# Channels_1_2.net
KiCad netlist of a schematic drawn in Altium Designer
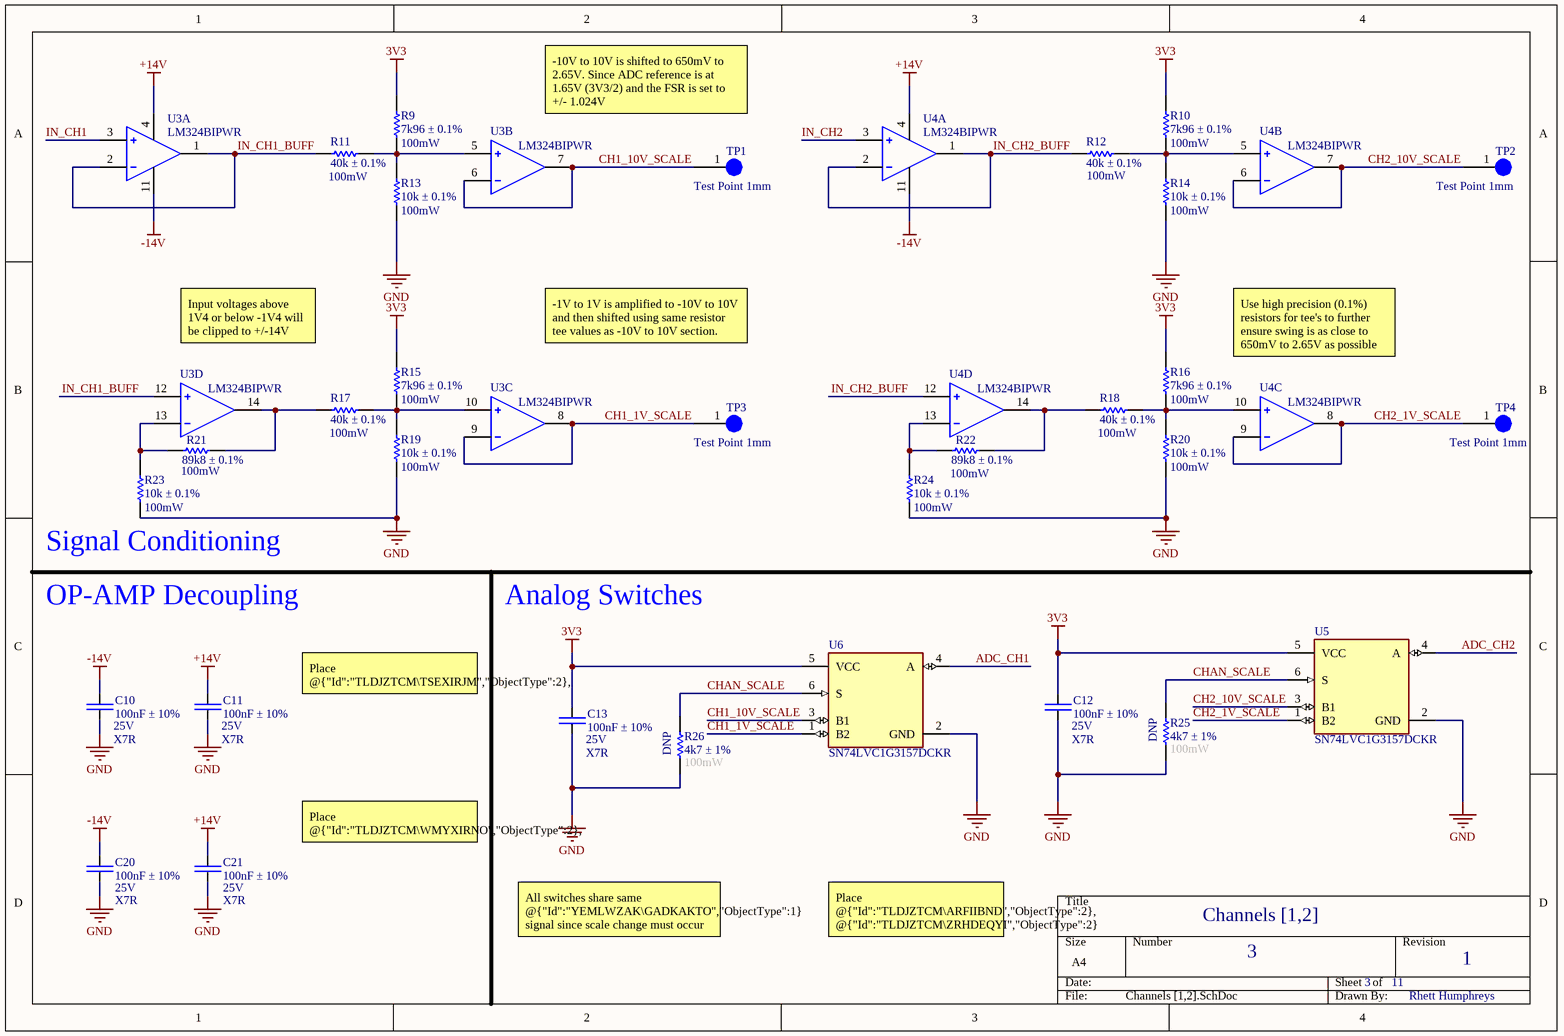
[diagram p0: Channels [1,2].SchDoc]

(export (version "E")
  (design (tool "Eeschema 10.0.6"))
  (components
    (comp (ref "C10")
      (value "100nF ± 10%")
      (footprint "CAP-0603")
      (description "Capacitor chip unpolarized. 0603")
      (libsource (lib "Master") (part "CAP-0603"))
    )
    (comp (ref "C11")
      (value "100nF ± 10%")
      (footprint "CAP-0603")
      (description "Capacitor chip unpolarized. 0603")
      (libsource (lib "Master") (part "CAP-0603"))
    )
    (comp (ref "C12")
      (value "100nF ± 10%")
      (footprint "CAP-0603")
      (description "Capacitor chip unpolarized. 0603")
      (libsource (lib "Master") (part "CAP-0603"))
    )
    (comp (ref "C13")
      (value "100nF ± 10%")
      (footprint "CAP-0603")
      (description "Capacitor chip unpolarized. 0603")
      (libsource (lib "Master") (part "CAP-0603"))
    )
    (comp (ref "C20")
      (value "100nF ± 10%")
      (footprint "CAP-0603")
      (description "Capacitor chip unpolarized. 0603")
      (libsource (lib "Master") (part "CAP-0603"))
    )
    (comp (ref "C21")
      (value "100nF ± 10%")
      (footprint "CAP-0603")
      (description "Capacitor chip unpolarized. 0603")
      (libsource (lib "Master") (part "CAP-0603"))
    )
    (comp (ref "R9")
      (value "7k96 ± 0.1%")
      (footprint "RES-0603")
      (description "Resistor chip. 0603")
      (libsource (lib "Master") (part "RES-0603"))
    )
    (comp (ref "R10")
      (value "7k96 ± 0.1%")
      (footprint "RES-0603")
      (description "Resistor chip. 0603")
      (libsource (lib "Master") (part "RES-0603"))
    )
    (comp (ref "R11")
      (value "40k ± 0.1%")
      (footprint "RES-0603")
      (description "Resistor chip. 0603")
      (libsource (lib "Master") (part "RES-0603"))
    )
    (comp (ref "R12")
      (value "40k ± 0.1%")
      (footprint "RES-0603")
      (description "Resistor chip. 0603")
      (libsource (lib "Master") (part "RES-0603"))
    )
    (comp (ref "R13")
      (value "10k ± 0.1%")
      (footprint "RES-0603")
      (description "Resistor chip. 0603")
      (libsource (lib "Master") (part "RES-0603"))
    )
    (comp (ref "R14")
      (value "10k ± 0.1%")
      (footprint "RES-0603")
      (description "Resistor chip. 0603")
      (libsource (lib "Master") (part "RES-0603"))
    )
    (comp (ref "R15")
      (value "7k96 ± 0.1%")
      (footprint "RES-0603")
      (description "Resistor chip. 0603")
      (libsource (lib "Master") (part "RES-0603"))
    )
    (comp (ref "R16")
      (value "7k96 ± 0.1%")
      (footprint "RES-0603")
      (description "Resistor chip. 0603")
      (libsource (lib "Master") (part "RES-0603"))
    )
    (comp (ref "R17")
      (value "40k ± 0.1%")
      (footprint "RES-0603")
      (description "Resistor chip. 0603")
      (libsource (lib "Master") (part "RES-0603"))
    )
    (comp (ref "R18")
      (value "40k ± 0.1%")
      (footprint "RES-0603")
      (description "Resistor chip. 0603")
      (libsource (lib "Master") (part "RES-0603"))
    )
    (comp (ref "R19")
      (value "10k ± 0.1%")
      (footprint "RES-0603")
      (description "Resistor chip. 0603")
      (libsource (lib "Master") (part "RES-0603"))
    )
    (comp (ref "R20")
      (value "10k ± 0.1%")
      (footprint "RES-0603")
      (description "Resistor chip. 0603")
      (libsource (lib "Master") (part "RES-0603"))
    )
    (comp (ref "R21")
      (value "89k8 ± 0.1%")
      (footprint "RES-0603")
      (description "Resistor chip. 0603")
      (libsource (lib "Master") (part "RES-0603"))
    )
    (comp (ref "R22")
      (value "89k8 ± 0.1%")
      (footprint "RES-0603")
      (description "Resistor chip. 0603")
      (libsource (lib "Master") (part "RES-0603"))
    )
    (comp (ref "R23")
      (value "10k ± 0.1%")
      (footprint "RES-0603")
      (description "Resistor chip. 0603")
      (libsource (lib "Master") (part "RES-0603"))
    )
    (comp (ref "R24")
      (value "10k ± 0.1%")
      (footprint "RES-0603")
      (description "Resistor chip. 0603")
      (libsource (lib "Master") (part "RES-0603"))
    )
    (comp (ref "R25")
      (value "4k7 ± 1%")
      (footprint "RES-0603")
      (description "Resistor chip. 0603")
      (libsource (lib "Master") (part "RES-0603"))
    )
    (comp (ref "R26")
      (value "4k7 ± 1%")
      (footprint "RES-0603")
      (description "Resistor chip. 0603")
      (libsource (lib "Master") (part "RES-0603"))
    )
    (comp (ref "TP1")
      (value "Test Point 1mm")
      (footprint "Test Point 1mm")
      (libsource (lib "Master") (part "Test Point 1mm"))
    )
    (comp (ref "TP2")
      (value "Test Point 1mm")
      (footprint "Test Point 1mm")
      (libsource (lib "Master") (part "Test Point 1mm"))
    )
    (comp (ref "TP3")
      (value "Test Point 1mm")
      (footprint "Test Point 1mm")
      (libsource (lib "Master") (part "Test Point 1mm"))
    )
    (comp (ref "TP4")
      (value "Test Point 1mm")
      (footprint "Test Point 1mm")
      (libsource (lib "Master") (part "Test Point 1mm"))
    )
    (comp (ref "U3")
      (value "LM324BIPWR")
      (footprint "FP-PW0014A-MFG")
      (description "LM324BIPWR Quad, 36-V, 1.2-MHz 3-mV offset voltage operational amplifier 14-TSSOP -40 to 85")
      (libsource (lib "Altium Content Vault") (part "9bf548ecc718f14caecb3de0839edcd"))
    )
    (comp (ref "U4")
      (value "LM324BIPWR")
      (footprint "FP-PW0014A-MFG")
      (description "LM324BIPWR Quad, 36-V, 1.2-MHz 3-mV offset voltage operational amplifier 14-TSSOP -40 to 85")
      (libsource (lib "Altium Content Vault") (part "9bf548ecc718f14caecb3de0839edcd"))
    )
    (comp (ref "U5")
      (value "SN74LVC1G3157DCKR")
      (footprint "FP-DCK0006A-IPC_B")
      (description "IC SWITCH SPDT SC70-6")
      (libsource (lib "Altium Content Vault") (part "0261a57985ab8eeec66806cf7caee19"))
    )
    (comp (ref "U6")
      (value "SN74LVC1G3157DCKR")
      (footprint "FP-DCK0006A-IPC_B")
      (description "IC SWITCH SPDT SC70-6")
      (libsource (lib "Altium Content Vault") (part "0261a57985ab8eeec66806cf7caee19"))
    )
  )
  (nets
    (net (code "1") (name "+14V") (class "Default")
      (node (ref "C11") (pin "2") (pintype "passive"))
      (node (ref "C21") (pin "2") (pintype "passive"))
      (node (ref "U3") (pin "4") (pinfunction "VCC+_4") (pintype "power_in"))
      (node (ref "U4") (pin "4") (pinfunction "VCC+_4") (pintype "power_in"))
    )
    (net (code "2") (name "-14V") (class "Default")
      (node (ref "C10") (pin "2") (pintype "passive"))
      (node (ref "C20") (pin "2") (pintype "passive"))
      (node (ref "U3") (pin "11") (pinfunction "VCC-_11") (pintype "power_in"))
      (node (ref "U4") (pin "11") (pinfunction "VCC-_11") (pintype "power_in"))
    )
    (net (code "3") (name "/ADC_CH1") (class "Default")
      (node (ref "U6") (pin "4") (pinfunction "A_4") (pintype "bidirectional"))
    )
    (net (code "4") (name "/ADC_CH2") (class "Default")
      (node (ref "U5") (pin "4") (pinfunction "A_4") (pintype "bidirectional"))
    )
    (net (code "5") (name "/CH1_1V_SCALE") (class "Default")
      (node (ref "TP3") (pin "1") (pintype "passive"))
      (node (ref "U3") (pin "8") (pinfunction "3OUT_8") (pintype "passive"))
      (node (ref "U3") (pin "9") (pinfunction "3IN-_9") (pintype "tri_state"))
      (node (ref "U6") (pin "1") (pinfunction "B2_1") (pintype "bidirectional"))
    )
    (net (code "6") (name "/CH1_10V_SCALE") (class "Default")
      (node (ref "TP1") (pin "1") (pintype "passive"))
      (node (ref "U3") (pin "6") (pinfunction "2IN-_6") (pintype "tri_state"))
      (node (ref "U3") (pin "7") (pinfunction "2OUT_7") (pintype "passive"))
      (node (ref "U6") (pin "3") (pinfunction "B1_3") (pintype "bidirectional"))
    )
    (net (code "7") (name "/CH2_1V_SCALE") (class "Default")
      (node (ref "TP4") (pin "1") (pintype "passive"))
      (node (ref "U4") (pin "8") (pinfunction "3OUT_8") (pintype "passive"))
      (node (ref "U4") (pin "9") (pinfunction "3IN-_9") (pintype "tri_state"))
      (node (ref "U5") (pin "1") (pinfunction "B2_1") (pintype "bidirectional"))
    )
    (net (code "8") (name "/CH2_10V_SCALE") (class "Default")
      (node (ref "TP2") (pin "1") (pintype "passive"))
      (node (ref "U4") (pin "6") (pinfunction "2IN-_6") (pintype "tri_state"))
      (node (ref "U4") (pin "7") (pinfunction "2OUT_7") (pintype "passive"))
      (node (ref "U5") (pin "3") (pinfunction "B1_3") (pintype "bidirectional"))
    )
    (net (code "9") (name "/CHAN_SCALE") (class "Default")
      (node (ref "R25") (pin "1") (pintype "passive"))
      (node (ref "R26") (pin "1") (pintype "passive"))
      (node (ref "U5") (pin "6") (pinfunction "S_6") (pintype "input"))
      (node (ref "U6") (pin "6") (pinfunction "S_6") (pintype "input"))
    )
    (net (code "10") (name "/IN_CH1") (class "Default")
      (node (ref "U3") (pin "3") (pinfunction "1IN+_3") (pintype "tri_state"))
    )
    (net (code "11") (name "/IN_CH1_BUFF") (class "Default")
      (node (ref "R11") (pin "2") (pintype "passive"))
      (node (ref "U3") (pin "1") (pinfunction "1OUT_1") (pintype "passive"))
      (node (ref "U3") (pin "12") (pinfunction "4IN+_12") (pintype "tri_state"))
      (node (ref "U3") (pin "2") (pinfunction "1IN-_2") (pintype "tri_state"))
    )
    (net (code "12") (name "/IN_CH2") (class "Default")
      (node (ref "U4") (pin "3") (pinfunction "1IN+_3") (pintype "tri_state"))
    )
    (net (code "13") (name "/IN_CH2_BUFF") (class "Default")
      (node (ref "R12") (pin "2") (pintype "passive"))
      (node (ref "U4") (pin "1") (pinfunction "1OUT_1") (pintype "passive"))
      (node (ref "U4") (pin "12") (pinfunction "4IN+_12") (pintype "tri_state"))
      (node (ref "U4") (pin "2") (pinfunction "1IN-_2") (pintype "tri_state"))
    )
    (net (code "14") (name "3V3") (class "Default")
      (node (ref "C12") (pin "2") (pintype "passive"))
      (node (ref "C13") (pin "2") (pintype "passive"))
      (node (ref "R10") (pin "1") (pintype "passive"))
      (node (ref "R15") (pin "1") (pintype "passive"))
      (node (ref "R16") (pin "1") (pintype "passive"))
      (node (ref "R9") (pin "1") (pintype "passive"))
      (node (ref "U5") (pin "5") (pinfunction "VCC_5") (pintype "power_in"))
      (node (ref "U6") (pin "5") (pinfunction "VCC_5") (pintype "power_in"))
    )
    (net (code "15") (name "GND") (class "Default")
      (node (ref "C10") (pin "1") (pintype "passive"))
      (node (ref "C11") (pin "1") (pintype "passive"))
      (node (ref "C12") (pin "1") (pintype "passive"))
      (node (ref "C13") (pin "1") (pintype "passive"))
      (node (ref "C20") (pin "1") (pintype "passive"))
      (node (ref "C21") (pin "1") (pintype "passive"))
      (node (ref "R13") (pin "2") (pintype "passive"))
      (node (ref "R14") (pin "2") (pintype "passive"))
      (node (ref "R19") (pin "2") (pintype "passive"))
      (node (ref "R20") (pin "2") (pintype "passive"))
      (node (ref "R23") (pin "2") (pintype "passive"))
      (node (ref "R24") (pin "2") (pintype "passive"))
      (node (ref "R25") (pin "2") (pintype "passive"))
      (node (ref "R26") (pin "2") (pintype "passive"))
      (node (ref "U5") (pin "2") (pinfunction "GND_2") (pintype "power_in"))
      (node (ref "U6") (pin "2") (pinfunction "GND_2") (pintype "power_in"))
    )
    (net (code "16") (name "Net-(U3B-2IN+)") (class "Default")
      (node (ref "R11") (pin "1") (pintype "passive"))
      (node (ref "R13") (pin "1") (pintype "passive"))
      (node (ref "R9") (pin "2") (pintype "passive"))
      (node (ref "U3") (pin "5") (pinfunction "2IN+_5") (pintype "tri_state"))
    )
    (net (code "17") (name "Net-(U3C-3IN+)") (class "Default")
      (node (ref "R15") (pin "2") (pintype "passive"))
      (node (ref "R17") (pin "1") (pintype "passive"))
      (node (ref "R19") (pin "1") (pintype "passive"))
      (node (ref "U3") (pin "10") (pinfunction "3IN+_10") (pintype "tri_state"))
    )
    (net (code "18") (name "Net-(U3D-4IN-)") (class "Default")
      (node (ref "R21") (pin "2") (pintype "passive"))
      (node (ref "R23") (pin "1") (pintype "passive"))
      (node (ref "U3") (pin "13") (pinfunction "4IN-_13") (pintype "tri_state"))
    )
    (net (code "19") (name "Net-(U3D-4OUT)") (class "Default")
      (node (ref "R17") (pin "2") (pintype "passive"))
      (node (ref "R21") (pin "1") (pintype "passive"))
      (node (ref "U3") (pin "14") (pinfunction "4OUT_14") (pintype "passive"))
    )
    (net (code "20") (name "Net-(U4B-2IN+)") (class "Default")
      (node (ref "R10") (pin "2") (pintype "passive"))
      (node (ref "R12") (pin "1") (pintype "passive"))
      (node (ref "R14") (pin "1") (pintype "passive"))
      (node (ref "U4") (pin "5") (pinfunction "2IN+_5") (pintype "tri_state"))
    )
    (net (code "21") (name "Net-(U4C-3IN+)") (class "Default")
      (node (ref "R16") (pin "2") (pintype "passive"))
      (node (ref "R18") (pin "1") (pintype "passive"))
      (node (ref "R20") (pin "1") (pintype "passive"))
      (node (ref "U4") (pin "10") (pinfunction "3IN+_10") (pintype "tri_state"))
    )
    (net (code "22") (name "Net-(U4D-4IN-)") (class "Default")
      (node (ref "R22") (pin "2") (pintype "passive"))
      (node (ref "R24") (pin "1") (pintype "passive"))
      (node (ref "U4") (pin "13") (pinfunction "4IN-_13") (pintype "tri_state"))
    )
    (net (code "23") (name "Net-(U4D-4OUT)") (class "Default")
      (node (ref "R18") (pin "2") (pintype "passive"))
      (node (ref "R22") (pin "1") (pintype "passive"))
      (node (ref "U4") (pin "14") (pinfunction "4OUT_14") (pintype "passive"))
    )
  )
)
